# RasPi-ADC_HAT_v10.net
KiCad netlist of a schematic drawn in EAGLE
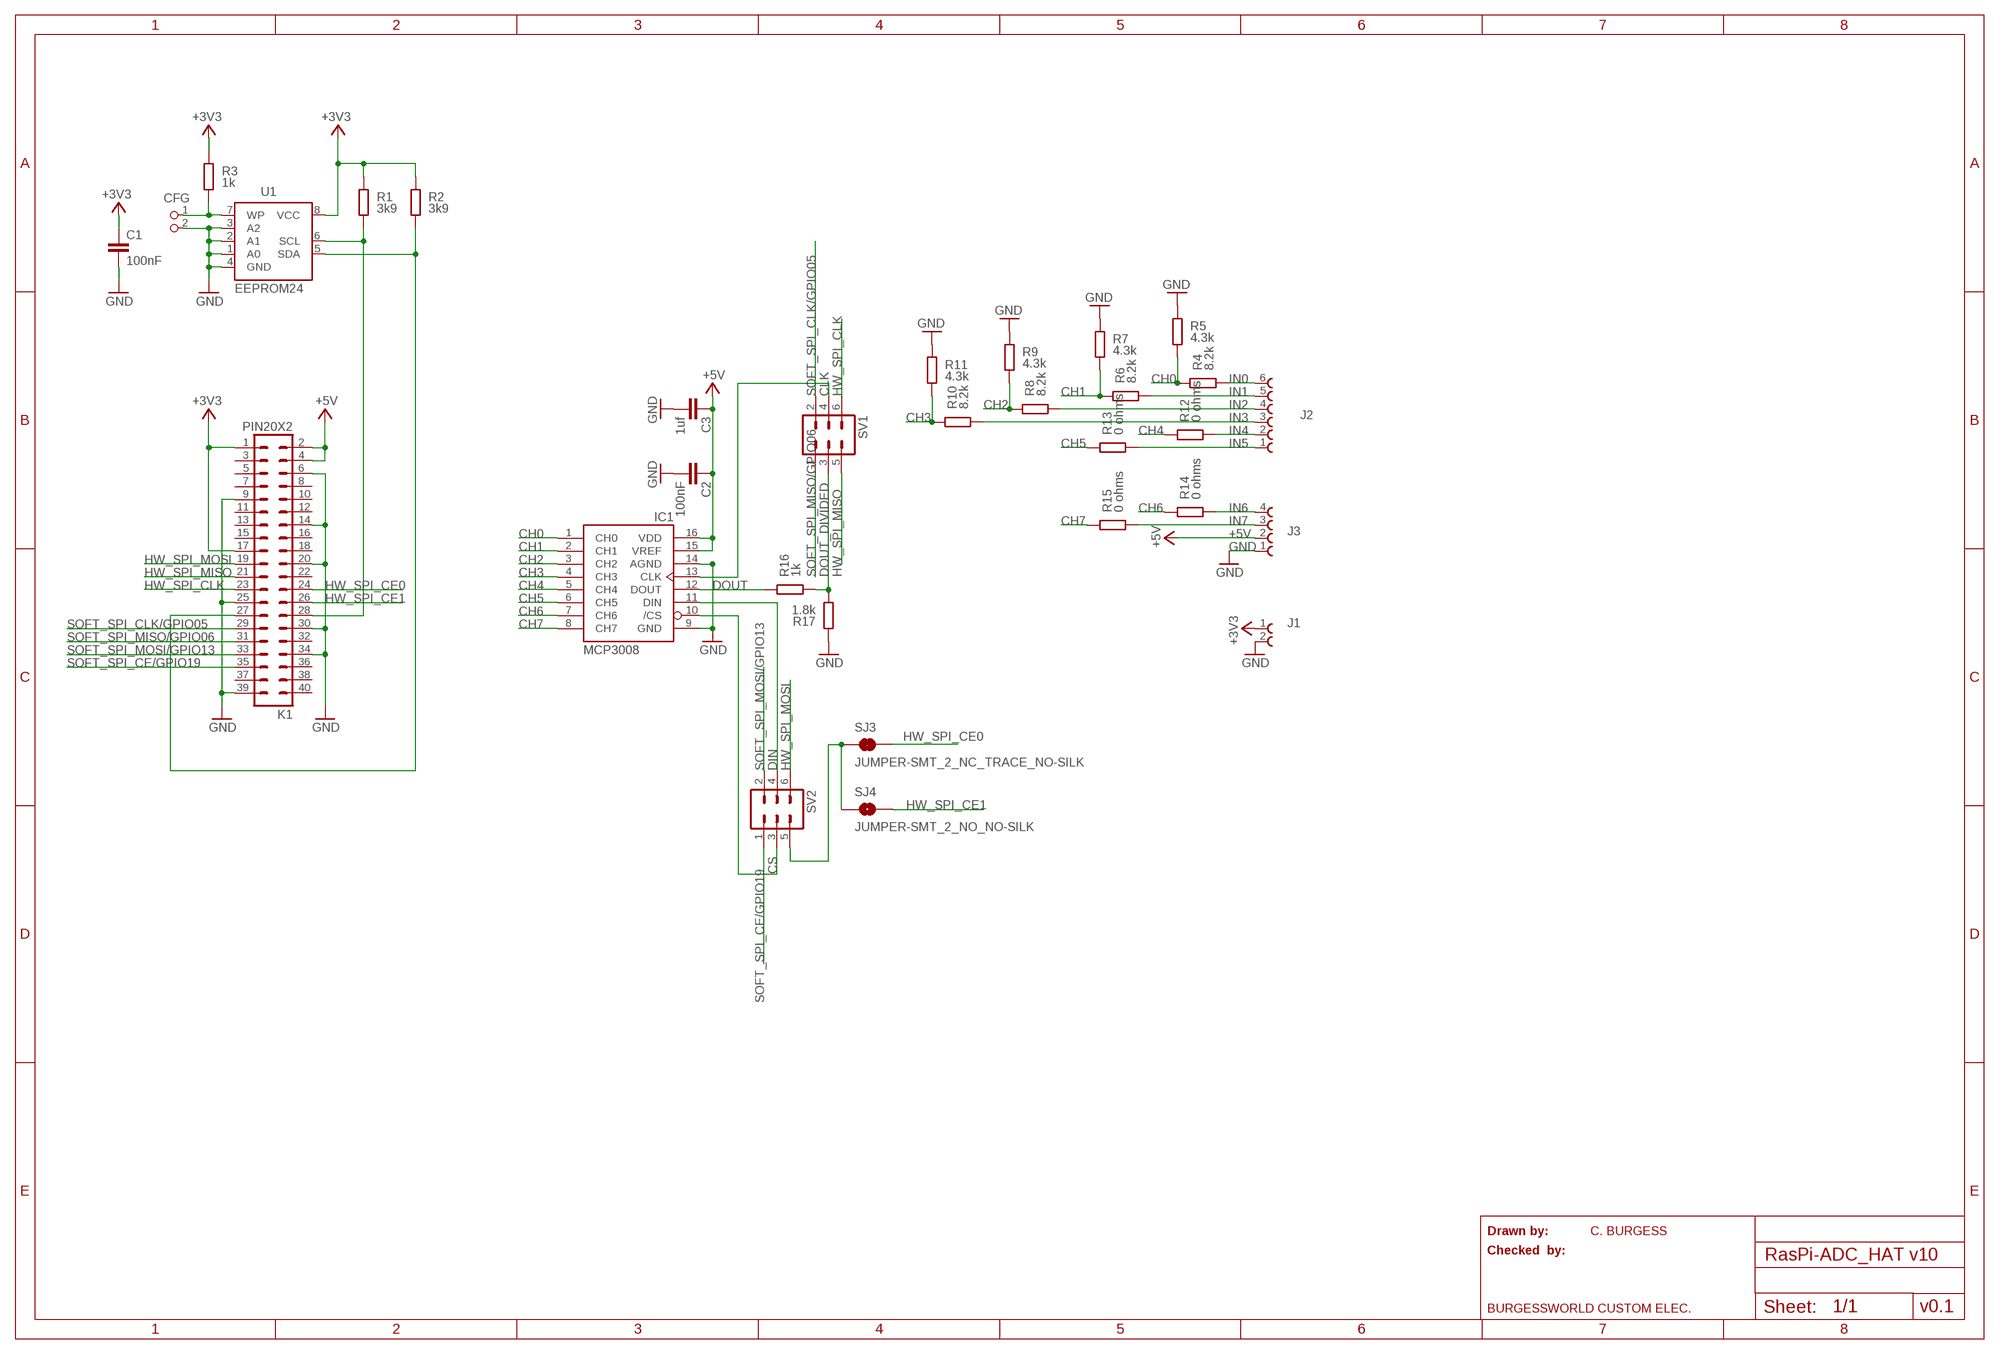
[diagram p0: schematic, sheet 1]

(export (version "E")
  (design (tool "Eeschema 10.0.6"))
  (components
    (comp (ref "C1")
      (value "100nF")
      (footprint "eagle-import:C0805K")
      (libsource (lib "eagle-import") (part "C-EUC0805K"))
    )
    (comp (ref "C2")
      (value "100nF")
      (footprint "eagle-import:C0805K")
      (libsource (lib "eagle-import") (part "C-EUC0805K"))
    )
    (comp (ref "C3")
      (value "1uf")
      (footprint "eagle-import:C0805K")
      (libsource (lib "eagle-import") (part "C-EUC0805K"))
    )
    (comp (ref "CFG")
      (value "PIN2_100")
      (footprint "eagle-import:PIN_W_2")
      (libsource (lib "eagle-import") (part "PIN2_100"))
    )
    (comp (ref "IC1")
      (value "MCP3008")
      (footprint "eagle-import:DIL16")
      (libsource (lib "eagle-import") (part "MCP3008"))
    )
    (comp (ref "J1")
      (value "691311500102")
      (footprint "eagle-import:691311500102")
      (libsource (lib "eagle-import") (part "691311500102"))
    )
    (comp (ref "J2")
      (value "691311500106")
      (footprint "eagle-import:691311500106")
      (libsource (lib "eagle-import") (part "691311500106"))
    )
    (comp (ref "J3")
      (value "691311500104")
      (footprint "eagle-import:691311500104")
      (libsource (lib "eagle-import") (part "691311500104"))
    )
    (comp (ref "K1")
      (value "PIN20X2")
      (footprint "eagle-import:PIN_20X2")
      (libsource (lib "eagle-import") (part "PIN20X2"))
    )
    (comp (ref "R1")
      (value "3k9")
      (footprint "eagle-import:M0805")
      (fields (field (name "TOLERANCE") "5%"))
      (libsource (lib "eagle-import") (part "R-EU_M0805"))
    )
    (comp (ref "R2")
      (value "3k9")
      (footprint "eagle-import:M0805")
      (fields (field (name "TOLERANCE") "5%"))
      (libsource (lib "eagle-import") (part "R-EU_M0805"))
    )
    (comp (ref "R3")
      (value "1k")
      (footprint "eagle-import:M0805")
      (fields (field (name "TOLERANCE") "5%"))
      (libsource (lib "eagle-import") (part "R-EU_M0805"))
    )
    (comp (ref "R4")
      (value "8.2k")
      (footprint "eagle-import:M0805")
      (fields (field (name "TOLERANCE") "5%"))
      (libsource (lib "eagle-import") (part "R-EU_M0805"))
    )
    (comp (ref "R5")
      (value "4.3k")
      (footprint "eagle-import:M0805")
      (fields (field (name "TOLERANCE") "5%"))
      (libsource (lib "eagle-import") (part "R-EU_M0805"))
    )
    (comp (ref "R6")
      (value "8.2k")
      (footprint "eagle-import:M0805")
      (fields (field (name "TOLERANCE") "5%"))
      (libsource (lib "eagle-import") (part "R-EU_M0805"))
    )
    (comp (ref "R7")
      (value "4.3k")
      (footprint "eagle-import:M0805")
      (fields (field (name "TOLERANCE") "5%"))
      (libsource (lib "eagle-import") (part "R-EU_M0805"))
    )
    (comp (ref "R8")
      (value "8.2k")
      (footprint "eagle-import:M0805")
      (fields (field (name "TOLERANCE") "5%"))
      (libsource (lib "eagle-import") (part "R-EU_M0805"))
    )
    (comp (ref "R9")
      (value "4.3k")
      (footprint "eagle-import:M0805")
      (fields (field (name "TOLERANCE") "5%"))
      (libsource (lib "eagle-import") (part "R-EU_M0805"))
    )
    (comp (ref "R10")
      (value "8.2k")
      (footprint "eagle-import:M0805")
      (fields (field (name "TOLERANCE") "5%"))
      (libsource (lib "eagle-import") (part "R-EU_M0805"))
    )
    (comp (ref "R11")
      (value "4.3k")
      (footprint "eagle-import:M0805")
      (fields (field (name "TOLERANCE") "5%"))
      (libsource (lib "eagle-import") (part "R-EU_M0805"))
    )
    (comp (ref "R12")
      (value "0 ohms")
      (footprint "eagle-import:M0805")
      (fields (field (name "TOLERANCE") "5%"))
      (libsource (lib "eagle-import") (part "R-EU_M0805"))
    )
    (comp (ref "R13")
      (value "0 ohms")
      (footprint "eagle-import:M0805")
      (fields (field (name "TOLERANCE") "5%"))
      (libsource (lib "eagle-import") (part "R-EU_M0805"))
    )
    (comp (ref "R14")
      (value "0 ohms")
      (footprint "eagle-import:M0805")
      (fields (field (name "TOLERANCE") "5%"))
      (libsource (lib "eagle-import") (part "R-EU_M0805"))
    )
    (comp (ref "R15")
      (value "0 ohms")
      (footprint "eagle-import:M0805")
      (fields (field (name "TOLERANCE") "5%"))
      (libsource (lib "eagle-import") (part "R-EU_M0805"))
    )
    (comp (ref "R16")
      (value "1k")
      (footprint "eagle-import:M0805")
      (fields (field (name "TOLERANCE") "5%"))
      (libsource (lib "eagle-import") (part "R-EU_M0805"))
    )
    (comp (ref "R17")
      (value "1.8k")
      (footprint "eagle-import:M0805")
      (fields (field (name "TOLERANCE") "5%"))
      (libsource (lib "eagle-import") (part "R-EU_M0805"))
    )
    (comp (ref "SJ3")
      (value "JUMPER-SMT_2_NC_TRACE_NO-SILK")
      (footprint "eagle-import:SMT-JUMPER_2_NC_TRACE_NO-SILK")
      (libsource (lib "eagle-import") (part "JUMPER-SMT_2_NC_TRACE_NO-SILK"))
    )
    (comp (ref "SJ4")
      (value "JUMPER-SMT_2_NO_NO-SILK")
      (footprint "eagle-import:SMT-JUMPER_2_NO_NO-SILK")
      (libsource (lib "eagle-import") (part "JUMPER-SMT_2_NO_NO-SILK"))
    )
    (comp (ref "SV1")
      (value "MA03-2")
      (footprint "eagle-import:MA03-2")
      (libsource (lib "eagle-import") (part "MA03-2"))
    )
    (comp (ref "SV2")
      (value "MA03-2")
      (footprint "eagle-import:MA03-2")
      (libsource (lib "eagle-import") (part "MA03-2"))
    )
    (comp (ref "U1")
      (value "EEPROM24")
      (footprint "eagle-import:SOIC8")
      (libsource (lib "eagle-import") (part "EEPROM24"))
    )
  )
  (nets
    (net (code "1") (name "+3V3") (class "Default")
      (node (ref "C1") (pin "1") (pinfunction "1_1") (pintype "passive"))
      (node (ref "J1") (pin "1") (pinfunction "1_1") (pintype "passive"))
      (node (ref "K1") (pin "1") (pinfunction "1_1") (pintype "passive"))
      (node (ref "K1") (pin "17") (pinfunction "17_17") (pintype "passive"))
      (node (ref "R1") (pin "2") (pinfunction "2_2") (pintype "passive"))
      (node (ref "R2") (pin "2") (pinfunction "2_2") (pintype "passive"))
      (node (ref "R3") (pin "2") (pinfunction "2_2") (pintype "passive"))
      (node (ref "U1") (pin "8") (pinfunction "VCC_8") (pintype "power_in"))
    )
    (net (code "2") (name "+5V") (class "Default")
      (node (ref "C2") (pin "1") (pinfunction "1_1") (pintype "passive"))
      (node (ref "C3") (pin "1") (pinfunction "1_1") (pintype "passive"))
      (node (ref "IC1") (pin "15") (pinfunction "VREF_15") (pintype "input"))
      (node (ref "IC1") (pin "16") (pinfunction "VDD_16") (pintype "power_in"))
      (node (ref "J3") (pin "2") (pinfunction "2_2") (pintype "passive"))
      (node (ref "K1") (pin "2") (pinfunction "2_2") (pintype "passive"))
      (node (ref "K1") (pin "4") (pinfunction "4_4") (pintype "passive"))
    )
    (net (code "3") (name "/CH0") (class "Default")
      (node (ref "IC1") (pin "1") (pinfunction "CH0_1") (pintype "input"))
      (node (ref "R4") (pin "2") (pinfunction "2_2") (pintype "passive"))
      (node (ref "R5") (pin "1") (pinfunction "1_1") (pintype "passive"))
    )
    (net (code "4") (name "/CH1") (class "Default")
      (node (ref "IC1") (pin "2") (pinfunction "CH1_2") (pintype "input"))
      (node (ref "R6") (pin "2") (pinfunction "2_2") (pintype "passive"))
      (node (ref "R7") (pin "1") (pinfunction "1_1") (pintype "passive"))
    )
    (net (code "5") (name "/CH2") (class "Default")
      (node (ref "IC1") (pin "3") (pinfunction "CH2_3") (pintype "input"))
      (node (ref "R8") (pin "2") (pinfunction "2_2") (pintype "passive"))
      (node (ref "R9") (pin "1") (pinfunction "1_1") (pintype "passive"))
    )
    (net (code "6") (name "/CH3") (class "Default")
      (node (ref "IC1") (pin "4") (pinfunction "CH3_4") (pintype "input"))
      (node (ref "R10") (pin "2") (pinfunction "2_2") (pintype "passive"))
      (node (ref "R11") (pin "1") (pinfunction "1_1") (pintype "passive"))
    )
    (net (code "7") (name "/CH4") (class "Default")
      (node (ref "IC1") (pin "5") (pinfunction "CH4_5") (pintype "input"))
      (node (ref "R12") (pin "2") (pinfunction "2_2") (pintype "passive"))
    )
    (net (code "8") (name "/CH5") (class "Default")
      (node (ref "IC1") (pin "6") (pinfunction "CH5_6") (pintype "input"))
      (node (ref "R13") (pin "2") (pinfunction "2_2") (pintype "passive"))
    )
    (net (code "9") (name "/CH6") (class "Default")
      (node (ref "IC1") (pin "7") (pinfunction "CH6_7") (pintype "input"))
      (node (ref "R14") (pin "2") (pinfunction "2_2") (pintype "passive"))
    )
    (net (code "10") (name "/CH7") (class "Default")
      (node (ref "IC1") (pin "8") (pinfunction "CH7_8") (pintype "input"))
      (node (ref "R15") (pin "2") (pinfunction "2_2") (pintype "passive"))
    )
    (net (code "11") (name "/CLK") (class "Default")
      (node (ref "IC1") (pin "13") (pinfunction "CLK_13") (pintype "input"))
      (node (ref "SV1") (pin "4") (pinfunction "4_4") (pintype "passive"))
    )
    (net (code "12") (name "/CS") (class "Default")
      (node (ref "IC1") (pin "10") (pinfunction "/CS_10") (pintype "input"))
      (node (ref "SV2") (pin "3") (pinfunction "3_3") (pintype "passive"))
    )
    (net (code "13") (name "/DIN") (class "Default")
      (node (ref "IC1") (pin "11") (pinfunction "DIN_11") (pintype "input"))
      (node (ref "SV2") (pin "4") (pinfunction "4_4") (pintype "passive"))
    )
    (net (code "14") (name "/DOUT") (class "Default")
      (node (ref "IC1") (pin "12") (pinfunction "DOUT_12") (pintype "output"))
      (node (ref "R16") (pin "2") (pinfunction "2_2") (pintype "passive"))
    )
    (net (code "15") (name "/DOUT_DIVIDED") (class "Default")
      (node (ref "R16") (pin "1") (pinfunction "1_1") (pintype "passive"))
      (node (ref "R17") (pin "1") (pinfunction "1_1") (pintype "passive"))
      (node (ref "SV1") (pin "3") (pinfunction "3_3") (pintype "passive"))
    )
    (net (code "16") (name "/HW_SPI_CE0") (class "Default")
      (node (ref "K1") (pin "24") (pinfunction "24_24") (pintype "passive"))
      (node (ref "SJ3") (pin "2") (pinfunction "2_2") (pintype "passive"))
    )
    (net (code "17") (name "/HW_SPI_CE1") (class "Default")
      (node (ref "K1") (pin "26") (pinfunction "26_26") (pintype "passive"))
      (node (ref "SJ4") (pin "2") (pinfunction "2_2") (pintype "passive"))
    )
    (net (code "18") (name "/HW_SPI_CLK") (class "Default")
      (node (ref "K1") (pin "23") (pinfunction "23_23") (pintype "passive"))
      (node (ref "SV1") (pin "6") (pinfunction "6_6") (pintype "passive"))
    )
    (net (code "19") (name "/HW_SPI_MISO") (class "Default")
      (node (ref "K1") (pin "21") (pinfunction "21_21") (pintype "passive"))
      (node (ref "SV1") (pin "5") (pinfunction "5_5") (pintype "passive"))
    )
    (net (code "20") (name "/HW_SPI_MOSI") (class "Default")
      (node (ref "K1") (pin "19") (pinfunction "19_19") (pintype "passive"))
      (node (ref "SV2") (pin "6") (pinfunction "6_6") (pintype "passive"))
    )
    (net (code "21") (name "/IN0") (class "Default")
      (node (ref "J2") (pin "6") (pinfunction "6_6") (pintype "passive"))
      (node (ref "R4") (pin "1") (pinfunction "1_1") (pintype "passive"))
    )
    (net (code "22") (name "/IN1") (class "Default")
      (node (ref "J2") (pin "5") (pinfunction "5_5") (pintype "passive"))
      (node (ref "R6") (pin "1") (pinfunction "1_1") (pintype "passive"))
    )
    (net (code "23") (name "/IN2") (class "Default")
      (node (ref "J2") (pin "4") (pinfunction "4_4") (pintype "passive"))
      (node (ref "R8") (pin "1") (pinfunction "1_1") (pintype "passive"))
    )
    (net (code "24") (name "/IN3") (class "Default")
      (node (ref "J2") (pin "3") (pinfunction "3_3") (pintype "passive"))
      (node (ref "R10") (pin "1") (pinfunction "1_1") (pintype "passive"))
    )
    (net (code "25") (name "/IN4") (class "Default")
      (node (ref "J2") (pin "2") (pinfunction "2_2") (pintype "passive"))
      (node (ref "R12") (pin "1") (pinfunction "1_1") (pintype "passive"))
    )
    (net (code "26") (name "/IN5") (class "Default")
      (node (ref "J2") (pin "1") (pinfunction "1_1") (pintype "passive"))
      (node (ref "R13") (pin "1") (pinfunction "1_1") (pintype "passive"))
    )
    (net (code "27") (name "/IN6") (class "Default")
      (node (ref "J3") (pin "4") (pinfunction "4_4") (pintype "passive"))
      (node (ref "R14") (pin "1") (pinfunction "1_1") (pintype "passive"))
    )
    (net (code "28") (name "/IN7") (class "Default")
      (node (ref "J3") (pin "3") (pinfunction "3_3") (pintype "passive"))
      (node (ref "R15") (pin "1") (pinfunction "1_1") (pintype "passive"))
    )
    (net (code "29") (name "/SOFT_SPI_CE{slash}GPIO19") (class "Default")
      (node (ref "K1") (pin "35") (pinfunction "35_35") (pintype "passive"))
      (node (ref "SV2") (pin "1") (pinfunction "1_1") (pintype "passive"))
    )
    (net (code "30") (name "/SOFT_SPI_CLK{slash}GPIO05") (class "Default")
      (node (ref "K1") (pin "29") (pinfunction "29_29") (pintype "passive"))
      (node (ref "SV1") (pin "2") (pinfunction "2_2") (pintype "passive"))
    )
    (net (code "31") (name "/SOFT_SPI_MISO{slash}GPIO06") (class "Default")
      (node (ref "K1") (pin "31") (pinfunction "31_31") (pintype "passive"))
      (node (ref "SV1") (pin "1") (pinfunction "1_1") (pintype "passive"))
    )
    (net (code "32") (name "/SOFT_SPI_MOSI{slash}GPIO13") (class "Default")
      (node (ref "K1") (pin "33") (pinfunction "33_33") (pintype "passive"))
      (node (ref "SV2") (pin "2") (pinfunction "2_2") (pintype "passive"))
    )
    (net (code "33") (name "GND") (class "Default")
      (node (ref "C1") (pin "2") (pinfunction "2_2") (pintype "passive"))
      (node (ref "C2") (pin "2") (pinfunction "2_2") (pintype "passive"))
      (node (ref "C3") (pin "2") (pinfunction "2_2") (pintype "passive"))
      (node (ref "CFG") (pin "2") (pinfunction "2_2") (pintype "passive"))
      (node (ref "IC1") (pin "14") (pinfunction "AGND_14") (pintype "power_in"))
      (node (ref "IC1") (pin "9") (pinfunction "GND_9") (pintype "power_in"))
      (node (ref "J1") (pin "2") (pinfunction "2_2") (pintype "passive"))
      (node (ref "J3") (pin "1") (pinfunction "1_1") (pintype "passive"))
      (node (ref "K1") (pin "14") (pinfunction "14_14") (pintype "passive"))
      (node (ref "K1") (pin "20") (pinfunction "20_20") (pintype "passive"))
      (node (ref "K1") (pin "25") (pinfunction "25_25") (pintype "passive"))
      (node (ref "K1") (pin "30") (pinfunction "30_30") (pintype "passive"))
      (node (ref "K1") (pin "34") (pinfunction "34_34") (pintype "passive"))
      (node (ref "K1") (pin "39") (pinfunction "39_39") (pintype "passive"))
      (node (ref "K1") (pin "6") (pinfunction "6_6") (pintype "passive"))
      (node (ref "K1") (pin "9") (pinfunction "9_9") (pintype "passive"))
      (node (ref "R11") (pin "2") (pinfunction "2_2") (pintype "passive"))
      (node (ref "R17") (pin "2") (pinfunction "2_2") (pintype "passive"))
      (node (ref "R5") (pin "2") (pinfunction "2_2") (pintype "passive"))
      (node (ref "R7") (pin "2") (pinfunction "2_2") (pintype "passive"))
      (node (ref "R9") (pin "2") (pinfunction "2_2") (pintype "passive"))
      (node (ref "U1") (pin "1") (pinfunction "A0_1") (pintype "input"))
      (node (ref "U1") (pin "2") (pinfunction "A1_2") (pintype "input"))
      (node (ref "U1") (pin "3") (pinfunction "A2_3") (pintype "input"))
      (node (ref "U1") (pin "4") (pinfunction "GND_4") (pintype "power_in"))
    )
    (net (code "34") (name "Net-(SJ3-Pad1)") (class "Default")
      (node (ref "SJ3") (pin "1") (pinfunction "1_1") (pintype "passive"))
      (node (ref "SJ4") (pin "1") (pinfunction "1_1") (pintype "passive"))
      (node (ref "SV2") (pin "5") (pinfunction "5_5") (pintype "passive"))
    )
    (net (code "35") (name "Net-(U1-SCL)") (class "Default")
      (node (ref "K1") (pin "28") (pinfunction "28_28") (pintype "passive"))
      (node (ref "R1") (pin "1") (pinfunction "1_1") (pintype "passive"))
      (node (ref "U1") (pin "6") (pinfunction "SCL_6") (pintype "input"))
    )
    (net (code "36") (name "Net-(U1-SDA)") (class "Default")
      (node (ref "K1") (pin "27") (pinfunction "27_27") (pintype "passive"))
      (node (ref "R2") (pin "1") (pinfunction "1_1") (pintype "passive"))
      (node (ref "U1") (pin "5") (pinfunction "SDA_5") (pintype "bidirectional"))
    )
    (net (code "37") (name "Net-(U1-WP)") (class "Default")
      (node (ref "CFG") (pin "1") (pinfunction "1_1") (pintype "passive"))
      (node (ref "R3") (pin "1") (pinfunction "1_1") (pintype "passive"))
      (node (ref "U1") (pin "7") (pinfunction "WP_7") (pintype "input"))
    )
    (net (code "38") (name "unconnected-(K1-Pad3)") (class "Default")
      (node (ref "K1") (pin "3") (pinfunction "3_3") (pintype "passive"))
    )
    (net (code "39") (name "unconnected-(K1-Pad5)") (class "Default")
      (node (ref "K1") (pin "5") (pinfunction "5_5") (pintype "passive"))
    )
    (net (code "40") (name "unconnected-(K1-Pad7)") (class "Default")
      (node (ref "K1") (pin "7") (pinfunction "7_7") (pintype "passive"))
    )
    (net (code "41") (name "unconnected-(K1-Pad8)") (class "Default")
      (node (ref "K1") (pin "8") (pinfunction "8_8") (pintype "passive"))
    )
    (net (code "42") (name "unconnected-(K1-Pad10)") (class "Default")
      (node (ref "K1") (pin "10") (pinfunction "10_10") (pintype "passive"))
    )
    (net (code "43") (name "unconnected-(K1-Pad11)") (class "Default")
      (node (ref "K1") (pin "11") (pinfunction "11_11") (pintype "passive"))
    )
    (net (code "44") (name "unconnected-(K1-Pad12)") (class "Default")
      (node (ref "K1") (pin "12") (pinfunction "12_12") (pintype "passive"))
    )
    (net (code "45") (name "unconnected-(K1-Pad13)") (class "Default")
      (node (ref "K1") (pin "13") (pinfunction "13_13") (pintype "passive"))
    )
    (net (code "46") (name "unconnected-(K1-Pad15)") (class "Default")
      (node (ref "K1") (pin "15") (pinfunction "15_15") (pintype "passive"))
    )
    (net (code "47") (name "unconnected-(K1-Pad16)") (class "Default")
      (node (ref "K1") (pin "16") (pinfunction "16_16") (pintype "passive"))
    )
    (net (code "48") (name "unconnected-(K1-Pad18)") (class "Default")
      (node (ref "K1") (pin "18") (pinfunction "18_18") (pintype "passive"))
    )
    (net (code "49") (name "unconnected-(K1-Pad22)") (class "Default")
      (node (ref "K1") (pin "22") (pinfunction "22_22") (pintype "passive"))
    )
    (net (code "50") (name "unconnected-(K1-Pad32)") (class "Default")
      (node (ref "K1") (pin "32") (pinfunction "32_32") (pintype "passive"))
    )
    (net (code "51") (name "unconnected-(K1-Pad36)") (class "Default")
      (node (ref "K1") (pin "36") (pinfunction "36_36") (pintype "passive"))
    )
    (net (code "52") (name "unconnected-(K1-Pad37)") (class "Default")
      (node (ref "K1") (pin "37") (pinfunction "37_37") (pintype "passive"))
    )
    (net (code "53") (name "unconnected-(K1-Pad38)") (class "Default")
      (node (ref "K1") (pin "38") (pinfunction "38_38") (pintype "passive"))
    )
    (net (code "54") (name "unconnected-(K1-Pad40)") (class "Default")
      (node (ref "K1") (pin "40") (pinfunction "40_40") (pintype "passive"))
    )
  )
)
